# Banks_11_12.net
KiCad netlist of a schematic drawn in Altium Designer
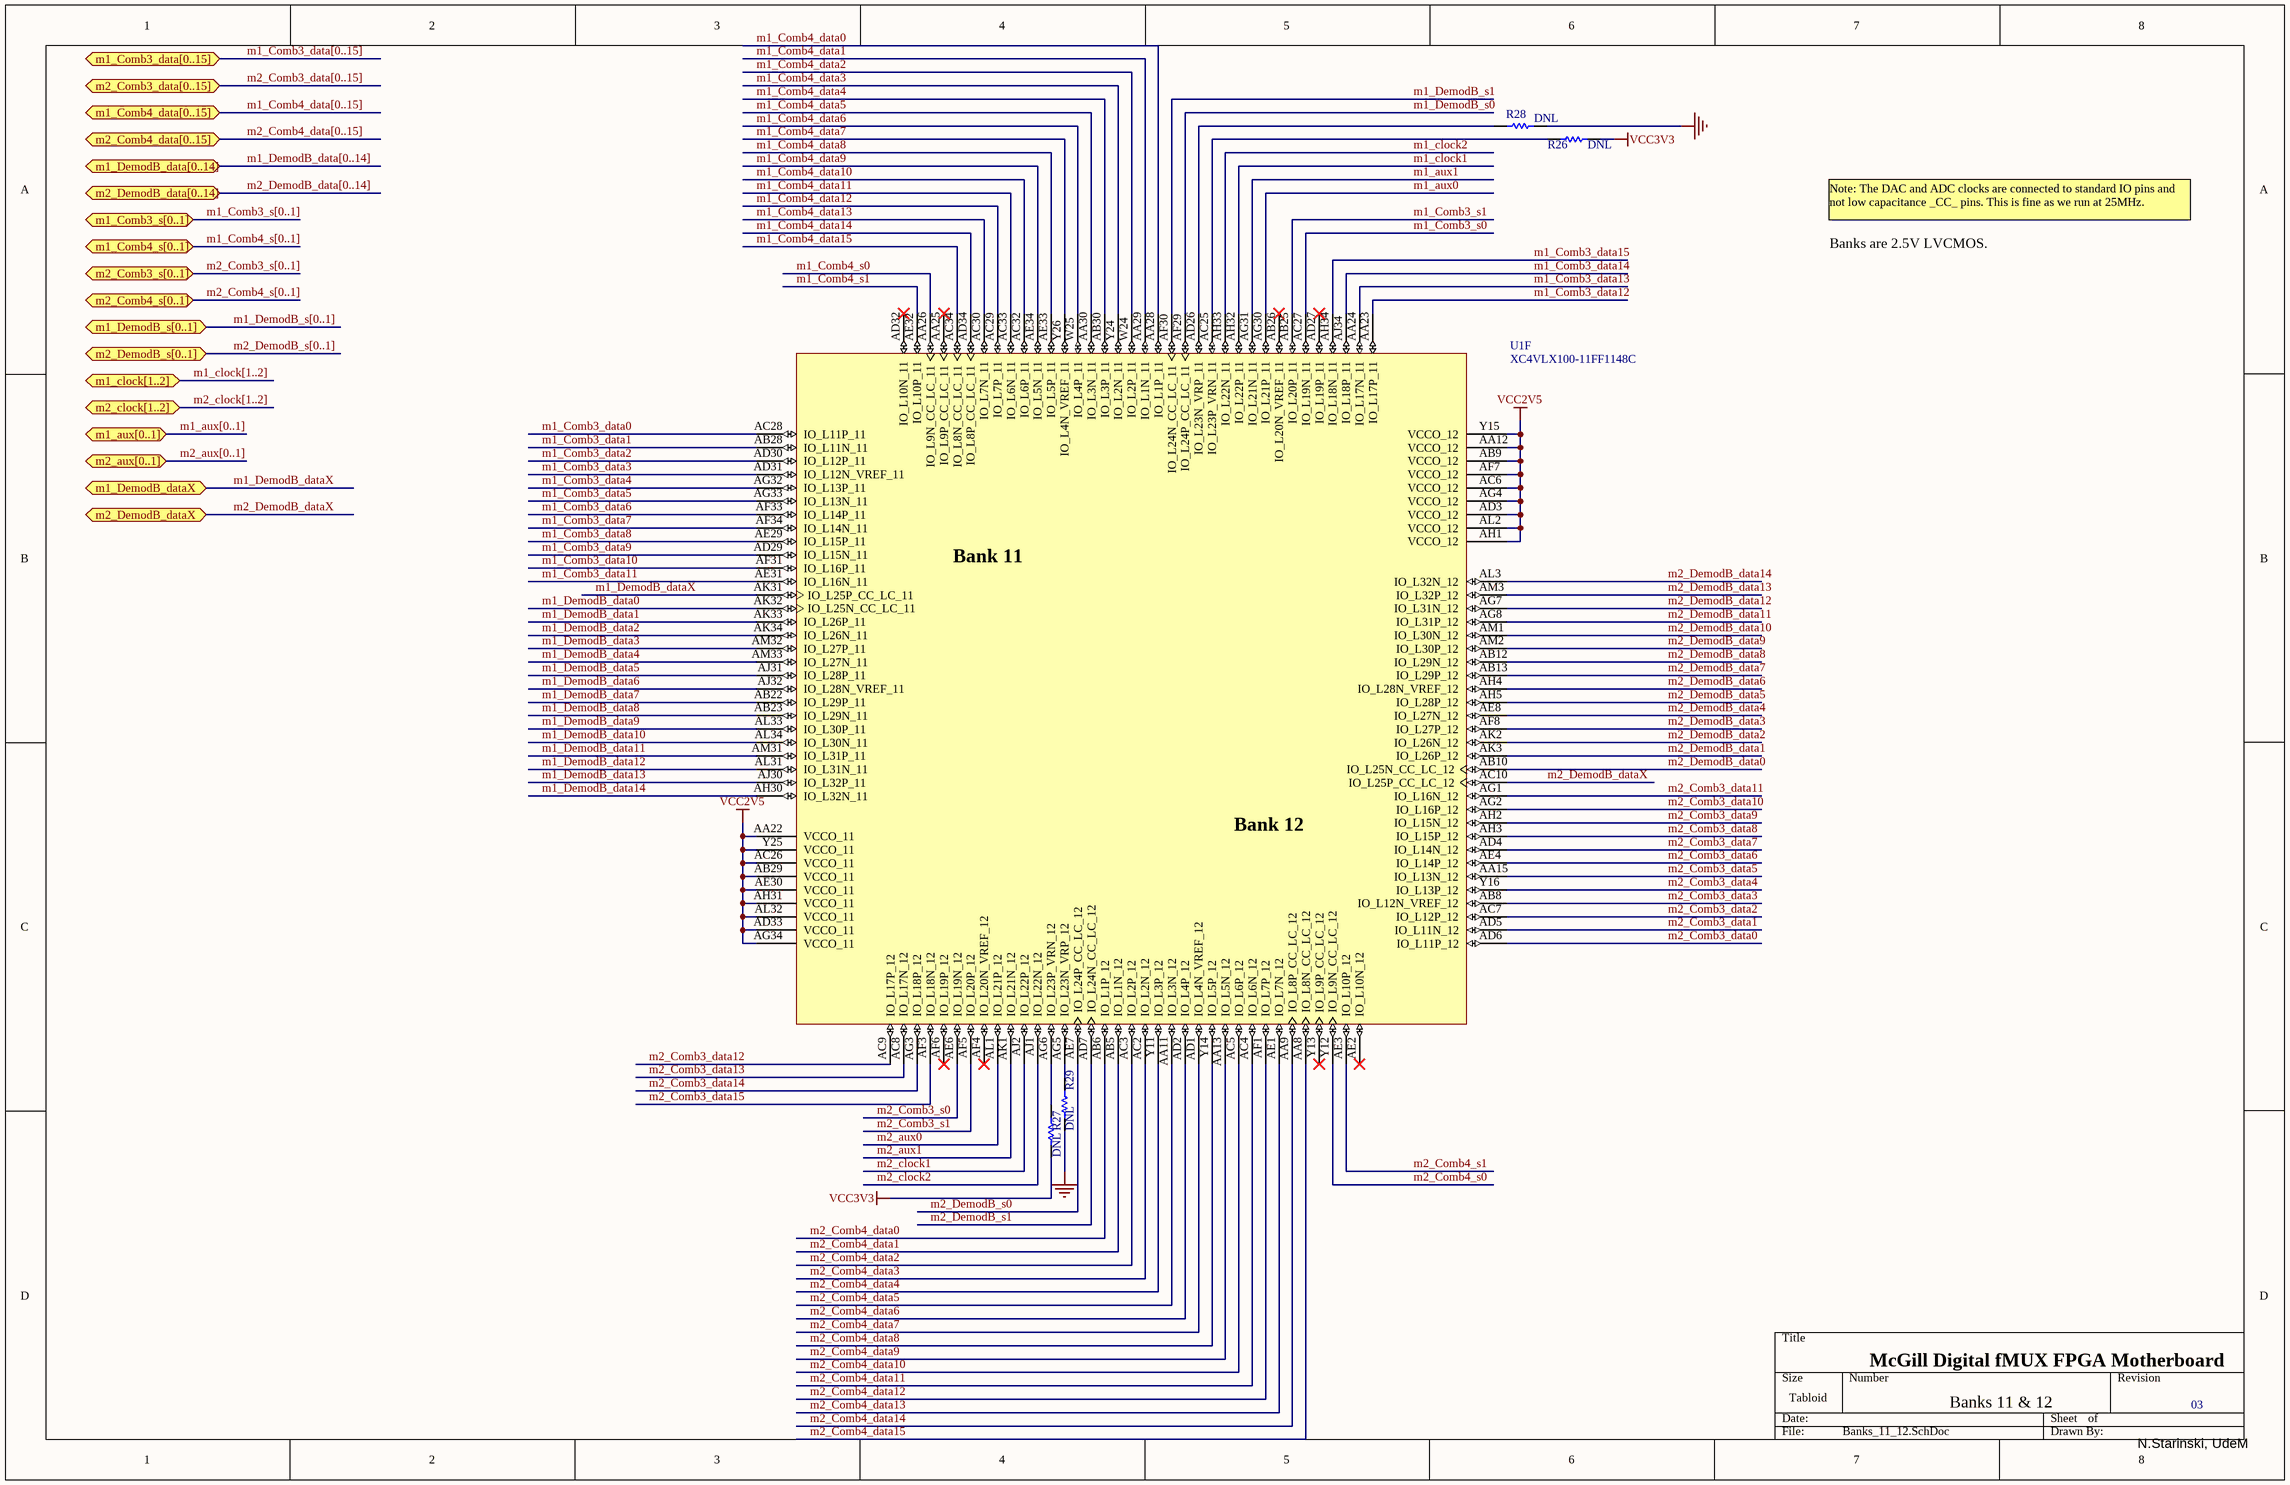
[diagram p0: Banks_11_12.SchDoc]

(export (version "E")
  (design (tool "Eeschema 10.0.6"))
  (components
    (comp (ref "R26")
      (value "DNL")
      (footprint "CR1608-0603")
      (description "Semiconductor Resistor")
      (fields (field (name "PUBLISHER") "Altium Limited"))
      (libsource (lib "Miscellaneous Devices") (part "Res Semi"))
    )
    (comp (ref "R27")
      (value "DNL")
      (footprint "CR1608-0603")
      (description "Semiconductor Resistor")
      (fields (field (name "PUBLISHER") "Altium Limited"))
      (libsource (lib "Miscellaneous Devices") (part "Res Semi"))
    )
    (comp (ref "R28")
      (value "DNL")
      (footprint "CR1608-0603")
      (description "Semiconductor Resistor")
      (fields (field (name "PUBLISHER") "Altium Limited"))
      (libsource (lib "Miscellaneous Devices") (part "Res Semi"))
    )
    (comp (ref "R29")
      (value "DNL")
      (footprint "CR1608-0603")
      (description "Semiconductor Resistor")
      (fields (field (name "PUBLISHER") "Altium Limited"))
      (libsource (lib "Miscellaneous Devices") (part "Res Semi"))
    )
    (comp (ref "U1")
      (value "XC4VLX100-11FF1148C")
      (footprint "FF1148")
      (description "Xilinx Virtex-4 LX Platform FPGA, 1148-Ball FFBGA, Speed Grade 11, 768 User I/Os, Commercial Grade")
      (fields (field (name "PUBLISHER") "Altium Limited"))
      (libsource (lib "Xilinx Virtex-4") (part "XC4VLX100-11FF1148C"))
    )
  )
  (nets
    (net (code "1") (name "/m1_Comb3_data0") (class "Default")
      (node (ref "U1") (pin "AC28") (pinfunction "IO_L11P_11_AC28") (pintype "bidirectional"))
    )
    (net (code "2") (name "/m1_Comb3_data1") (class "Default")
      (node (ref "U1") (pin "AB28") (pinfunction "IO_L11N_11_AB28") (pintype "bidirectional"))
    )
    (net (code "3") (name "/m1_Comb3_data2") (class "Default")
      (node (ref "U1") (pin "AD30") (pinfunction "IO_L12P_11_AD30") (pintype "bidirectional"))
    )
    (net (code "4") (name "/m1_Comb3_data3") (class "Default")
      (node (ref "U1") (pin "AD31") (pinfunction "IO_L12N_VREF_11_AD31") (pintype "bidirectional"))
    )
    (net (code "5") (name "/m1_Comb3_data4") (class "Default")
      (node (ref "U1") (pin "AG32") (pinfunction "IO_L13P_11_AG32") (pintype "bidirectional"))
    )
    (net (code "6") (name "/m1_Comb3_data5") (class "Default")
      (node (ref "U1") (pin "AG33") (pinfunction "IO_L13N_11_AG33") (pintype "bidirectional"))
    )
    (net (code "7") (name "/m1_Comb3_data6") (class "Default")
      (node (ref "U1") (pin "AF33") (pinfunction "IO_L14P_11_AF33") (pintype "bidirectional"))
    )
    (net (code "8") (name "/m1_Comb3_data7") (class "Default")
      (node (ref "U1") (pin "AF34") (pinfunction "IO_L14N_11_AF34") (pintype "bidirectional"))
    )
    (net (code "9") (name "/m1_Comb3_data8") (class "Default")
      (node (ref "U1") (pin "AE29") (pinfunction "IO_L15P_11_AE29") (pintype "bidirectional"))
    )
    (net (code "10") (name "/m1_Comb3_data9") (class "Default")
      (node (ref "U1") (pin "AD29") (pinfunction "IO_L15N_11_AD29") (pintype "bidirectional"))
    )
    (net (code "11") (name "/m1_Comb3_data10") (class "Default")
      (node (ref "U1") (pin "AF31") (pinfunction "IO_L16P_11_AF31") (pintype "bidirectional"))
    )
    (net (code "12") (name "/m1_Comb3_data11") (class "Default")
      (node (ref "U1") (pin "AE31") (pinfunction "IO_L16N_11_AE31") (pintype "bidirectional"))
    )
    (net (code "13") (name "/m1_Comb3_data12") (class "Default")
      (node (ref "U1") (pin "AA23") (pinfunction "IO_L17P_11_AA23") (pintype "bidirectional"))
    )
    (net (code "14") (name "/m1_Comb3_data13") (class "Default")
      (node (ref "U1") (pin "AA24") (pinfunction "IO_L17N_11_AA24") (pintype "bidirectional"))
    )
    (net (code "15") (name "/m1_Comb3_data14") (class "Default")
      (node (ref "U1") (pin "AJ34") (pinfunction "IO_L18P_11_AJ34") (pintype "bidirectional"))
    )
    (net (code "16") (name "/m1_Comb3_data15") (class "Default")
      (node (ref "U1") (pin "AH34") (pinfunction "IO_L18N_11_AH34") (pintype "bidirectional"))
    )
    (net (code "18") (name "/m1_Comb3_s0") (class "Default")
      (node (ref "U1") (pin "AC27") (pinfunction "IO_L19N_11_AC27") (pintype "bidirectional"))
    )
    (net (code "19") (name "/m1_Comb3_s1") (class "Default")
      (node (ref "U1") (pin "AB25") (pinfunction "IO_L20P_11_AB25") (pintype "bidirectional"))
    )
    (net (code "21") (name "/m1_Comb4_data0") (class "Default")
      (node (ref "U1") (pin "AA28") (pinfunction "IO_L1P_11_AA28") (pintype "bidirectional"))
    )
    (net (code "22") (name "/m1_Comb4_data1") (class "Default")
      (node (ref "U1") (pin "AA29") (pinfunction "IO_L1N_11_AA29") (pintype "bidirectional"))
    )
    (net (code "23") (name "/m1_Comb4_data2") (class "Default")
      (node (ref "U1") (pin "W24") (pinfunction "IO_L2P_11_W24") (pintype "bidirectional"))
    )
    (net (code "24") (name "/m1_Comb4_data3") (class "Default")
      (node (ref "U1") (pin "Y24") (pinfunction "IO_L2N_11_Y24") (pintype "bidirectional"))
    )
    (net (code "25") (name "/m1_Comb4_data4") (class "Default")
      (node (ref "U1") (pin "AB30") (pinfunction "IO_L3P_11_AB30") (pintype "bidirectional"))
    )
    (net (code "26") (name "/m1_Comb4_data5") (class "Default")
      (node (ref "U1") (pin "AA30") (pinfunction "IO_L3N_11_AA30") (pintype "bidirectional"))
    )
    (net (code "27") (name "/m1_Comb4_data6") (class "Default")
      (node (ref "U1") (pin "W25") (pinfunction "IO_L4P_11_W25") (pintype "bidirectional"))
    )
    (net (code "28") (name "/m1_Comb4_data7") (class "Default")
      (node (ref "U1") (pin "Y26") (pinfunction "IO_L4N_VREF_11_Y26") (pintype "bidirectional"))
    )
    (net (code "29") (name "/m1_Comb4_data8") (class "Default")
      (node (ref "U1") (pin "AE33") (pinfunction "IO_L5P_11_AE33") (pintype "bidirectional"))
    )
    (net (code "30") (name "/m1_Comb4_data9") (class "Default")
      (node (ref "U1") (pin "AE34") (pinfunction "IO_L5N_11_AE34") (pintype "bidirectional"))
    )
    (net (code "31") (name "/m1_Comb4_data10") (class "Default")
      (node (ref "U1") (pin "AC32") (pinfunction "IO_L6P_11_AC32") (pintype "bidirectional"))
    )
    (net (code "32") (name "/m1_Comb4_data11") (class "Default")
      (node (ref "U1") (pin "AC33") (pinfunction "IO_L6N_11_AC33") (pintype "bidirectional"))
    )
    (net (code "33") (name "/m1_Comb4_data12") (class "Default")
      (node (ref "U1") (pin "AC29") (pinfunction "IO_L7P_11_AC29") (pintype "bidirectional"))
    )
    (net (code "34") (name "/m1_Comb4_data13") (class "Default")
      (node (ref "U1") (pin "AC30") (pinfunction "IO_L7N_11_AC30") (pintype "bidirectional"))
    )
    (net (code "35") (name "/m1_Comb4_data14") (class "Default")
      (node (ref "U1") (pin "AD34") (pinfunction "IO_L8P_CC_LC_11_AD34") (pintype "bidirectional"))
    )
    (net (code "36") (name "/m1_Comb4_data15") (class "Default")
      (node (ref "U1") (pin "AC34") (pinfunction "IO_L8N_CC_LC_11_AC34") (pintype "bidirectional"))
    )
    (net (code "38") (name "/m1_Comb4_s0") (class "Default")
      (node (ref "U1") (pin "AA26") (pinfunction "IO_L9N_CC_LC_11_AA26") (pintype "bidirectional"))
    )
    (net (code "39") (name "/m1_Comb4_s1") (class "Default")
      (node (ref "U1") (pin "AE32") (pinfunction "IO_L10P_11_AE32") (pintype "bidirectional"))
    )
    (net (code "41") (name "/m1_DemodB_data0") (class "Default")
      (node (ref "U1") (pin "AK32") (pinfunction "IO_L25N_CC_LC_11_AK32") (pintype "bidirectional"))
    )
    (net (code "42") (name "/m1_DemodB_data1") (class "Default")
      (node (ref "U1") (pin "AK33") (pinfunction "IO_L26P_11_AK33") (pintype "bidirectional"))
    )
    (net (code "43") (name "/m1_DemodB_data2") (class "Default")
      (node (ref "U1") (pin "AK34") (pinfunction "IO_L26N_11_AK34") (pintype "bidirectional"))
    )
    (net (code "44") (name "/m1_DemodB_data3") (class "Default")
      (node (ref "U1") (pin "AM32") (pinfunction "IO_L27P_11_AM32") (pintype "bidirectional"))
    )
    (net (code "45") (name "/m1_DemodB_data4") (class "Default")
      (node (ref "U1") (pin "AM33") (pinfunction "IO_L27N_11_AM33") (pintype "bidirectional"))
    )
    (net (code "46") (name "/m1_DemodB_data5") (class "Default")
      (node (ref "U1") (pin "AJ31") (pinfunction "IO_L28P_11_AJ31") (pintype "bidirectional"))
    )
    (net (code "47") (name "/m1_DemodB_data6") (class "Default")
      (node (ref "U1") (pin "AJ32") (pinfunction "IO_L28N_VREF_11_AJ32") (pintype "bidirectional"))
    )
    (net (code "48") (name "/m1_DemodB_data7") (class "Default")
      (node (ref "U1") (pin "AB22") (pinfunction "IO_L29P_11_AB22") (pintype "bidirectional"))
    )
    (net (code "49") (name "/m1_DemodB_data8") (class "Default")
      (node (ref "U1") (pin "AB23") (pinfunction "IO_L29N_11_AB23") (pintype "bidirectional"))
    )
    (net (code "50") (name "/m1_DemodB_data9") (class "Default")
      (node (ref "U1") (pin "AL33") (pinfunction "IO_L30P_11_AL33") (pintype "bidirectional"))
    )
    (net (code "51") (name "/m1_DemodB_data10") (class "Default")
      (node (ref "U1") (pin "AL34") (pinfunction "IO_L30N_11_AL34") (pintype "bidirectional"))
    )
    (net (code "52") (name "/m1_DemodB_data11") (class "Default")
      (node (ref "U1") (pin "AM31") (pinfunction "IO_L31P_11_AM31") (pintype "bidirectional"))
    )
    (net (code "53") (name "/m1_DemodB_data12") (class "Default")
      (node (ref "U1") (pin "AL31") (pinfunction "IO_L31N_11_AL31") (pintype "bidirectional"))
    )
    (net (code "54") (name "/m1_DemodB_data13") (class "Default")
      (node (ref "U1") (pin "AJ30") (pinfunction "IO_L32P_11_AJ30") (pintype "bidirectional"))
    )
    (net (code "55") (name "/m1_DemodB_data14") (class "Default")
      (node (ref "U1") (pin "AH30") (pinfunction "IO_L32N_11_AH30") (pintype "bidirectional"))
    )
    (net (code "56") (name "/m1_DemodB_dataX") (class "Default")
      (node (ref "U1") (pin "AK31") (pinfunction "IO_L25P_CC_LC_11_AK31") (pintype "bidirectional"))
    )
    (net (code "58") (name "/m1_DemodB_s0") (class "Default")
      (node (ref "U1") (pin "AF29") (pinfunction "IO_L24P_CC_LC_11_AF29") (pintype "bidirectional"))
    )
    (net (code "59") (name "/m1_DemodB_s1") (class "Default")
      (node (ref "U1") (pin "AF30") (pinfunction "IO_L24N_CC_LC_11_AF30") (pintype "bidirectional"))
    )
    (net (code "61") (name "/m1_aux0") (class "Default")
      (node (ref "U1") (pin "AG30") (pinfunction "IO_L21P_11_AG30") (pintype "bidirectional"))
    )
    (net (code "62") (name "/m1_aux1") (class "Default")
      (node (ref "U1") (pin "AG31") (pinfunction "IO_L21N_11_AG31") (pintype "bidirectional"))
    )
    (net (code "64") (name "/m1_clock1") (class "Default")
      (node (ref "U1") (pin "AH32") (pinfunction "IO_L22P_11_AH32") (pintype "bidirectional"))
    )
    (net (code "65") (name "/m1_clock2") (class "Default")
      (node (ref "U1") (pin "AH33") (pinfunction "IO_L22N_11_AH33") (pintype "bidirectional"))
    )
    (net (code "67") (name "/m2_Comb3_data0") (class "Default")
      (node (ref "U1") (pin "AD6") (pinfunction "IO_L11P_12_AD6") (pintype "bidirectional"))
    )
    (net (code "68") (name "/m2_Comb3_data1") (class "Default")
      (node (ref "U1") (pin "AD5") (pinfunction "IO_L11N_12_AD5") (pintype "bidirectional"))
    )
    (net (code "69") (name "/m2_Comb3_data2") (class "Default")
      (node (ref "U1") (pin "AC7") (pinfunction "IO_L12P_12_AC7") (pintype "bidirectional"))
    )
    (net (code "70") (name "/m2_Comb3_data3") (class "Default")
      (node (ref "U1") (pin "AB8") (pinfunction "IO_L12N_VREF_12_AB8") (pintype "bidirectional"))
    )
    (net (code "71") (name "/m2_Comb3_data4") (class "Default")
      (node (ref "U1") (pin "Y16") (pinfunction "IO_L13P_12_Y16") (pintype "bidirectional"))
    )
    (net (code "72") (name "/m2_Comb3_data5") (class "Default")
      (node (ref "U1") (pin "AA15") (pinfunction "IO_L13N_12_AA15") (pintype "bidirectional"))
    )
    (net (code "73") (name "/m2_Comb3_data6") (class "Default")
      (node (ref "U1") (pin "AE4") (pinfunction "IO_L14P_12_AE4") (pintype "bidirectional"))
    )
    (net (code "74") (name "/m2_Comb3_data7") (class "Default")
      (node (ref "U1") (pin "AD4") (pinfunction "IO_L14N_12_AD4") (pintype "bidirectional"))
    )
    (net (code "75") (name "/m2_Comb3_data8") (class "Default")
      (node (ref "U1") (pin "AH3") (pinfunction "IO_L15P_12_AH3") (pintype "bidirectional"))
    )
    (net (code "76") (name "/m2_Comb3_data9") (class "Default")
      (node (ref "U1") (pin "AH2") (pinfunction "IO_L15N_12_AH2") (pintype "bidirectional"))
    )
    (net (code "77") (name "/m2_Comb3_data10") (class "Default")
      (node (ref "U1") (pin "AG2") (pinfunction "IO_L16P_12_AG2") (pintype "bidirectional"))
    )
    (net (code "78") (name "/m2_Comb3_data11") (class "Default")
      (node (ref "U1") (pin "AG1") (pinfunction "IO_L16N_12_AG1") (pintype "bidirectional"))
    )
    (net (code "79") (name "/m2_Comb3_data12") (class "Default")
      (node (ref "U1") (pin "AC9") (pinfunction "IO_L17P_12_AC9") (pintype "bidirectional"))
    )
    (net (code "80") (name "/m2_Comb3_data13") (class "Default")
      (node (ref "U1") (pin "AC8") (pinfunction "IO_L17N_12_AC8") (pintype "bidirectional"))
    )
    (net (code "81") (name "/m2_Comb3_data14") (class "Default")
      (node (ref "U1") (pin "AG3") (pinfunction "IO_L18P_12_AG3") (pintype "bidirectional"))
    )
    (net (code "82") (name "/m2_Comb3_data15") (class "Default")
      (node (ref "U1") (pin "AF3") (pinfunction "IO_L18N_12_AF3") (pintype "bidirectional"))
    )
    (net (code "84") (name "/m2_Comb3_s0") (class "Default")
      (node (ref "U1") (pin "AE6") (pinfunction "IO_L19N_12_AE6") (pintype "bidirectional"))
    )
    (net (code "85") (name "/m2_Comb3_s1") (class "Default")
      (node (ref "U1") (pin "AF5") (pinfunction "IO_L20P_12_AF5") (pintype "bidirectional"))
    )
    (net (code "87") (name "/m2_Comb4_data0") (class "Default")
      (node (ref "U1") (pin "AB6") (pinfunction "IO_L1P_12_AB6") (pintype "bidirectional"))
    )
    (net (code "88") (name "/m2_Comb4_data1") (class "Default")
      (node (ref "U1") (pin "AB5") (pinfunction "IO_L1N_12_AB5") (pintype "bidirectional"))
    )
    (net (code "89") (name "/m2_Comb4_data2") (class "Default")
      (node (ref "U1") (pin "AC3") (pinfunction "IO_L2P_12_AC3") (pintype "bidirectional"))
    )
    (net (code "90") (name "/m2_Comb4_data3") (class "Default")
      (node (ref "U1") (pin "AC2") (pinfunction "IO_L2N_12_AC2") (pintype "bidirectional"))
    )
    (net (code "91") (name "/m2_Comb4_data4") (class "Default")
      (node (ref "U1") (pin "Y11") (pinfunction "IO_L3P_12_Y11") (pintype "bidirectional"))
    )
    (net (code "92") (name "/m2_Comb4_data5") (class "Default")
      (node (ref "U1") (pin "AA11") (pinfunction "IO_L3N_12_AA11") (pintype "bidirectional"))
    )
    (net (code "93") (name "/m2_Comb4_data6") (class "Default")
      (node (ref "U1") (pin "AD2") (pinfunction "IO_L4P_12_AD2") (pintype "bidirectional"))
    )
    (net (code "94") (name "/m2_Comb4_data7") (class "Default")
      (node (ref "U1") (pin "AD1") (pinfunction "IO_L4N_VREF_12_AD1") (pintype "bidirectional"))
    )
    (net (code "95") (name "/m2_Comb4_data8") (class "Default")
      (node (ref "U1") (pin "Y14") (pinfunction "IO_L5P_12_Y14") (pintype "bidirectional"))
    )
    (net (code "96") (name "/m2_Comb4_data9") (class "Default")
      (node (ref "U1") (pin "AA13") (pinfunction "IO_L5N_12_AA13") (pintype "bidirectional"))
    )
    (net (code "97") (name "/m2_Comb4_data10") (class "Default")
      (node (ref "U1") (pin "AC5") (pinfunction "IO_L6P_12_AC5") (pintype "bidirectional"))
    )
    (net (code "98") (name "/m2_Comb4_data11") (class "Default")
      (node (ref "U1") (pin "AC4") (pinfunction "IO_L6N_12_AC4") (pintype "bidirectional"))
    )
    (net (code "99") (name "/m2_Comb4_data12") (class "Default")
      (node (ref "U1") (pin "AF1") (pinfunction "IO_L7P_12_AF1") (pintype "bidirectional"))
    )
    (net (code "100") (name "/m2_Comb4_data13") (class "Default")
      (node (ref "U1") (pin "AE1") (pinfunction "IO_L7N_12_AE1") (pintype "bidirectional"))
    )
    (net (code "101") (name "/m2_Comb4_data14") (class "Default")
      (node (ref "U1") (pin "AA9") (pinfunction "IO_L8P_CC_LC_12_AA9") (pintype "bidirectional"))
    )
    (net (code "102") (name "/m2_Comb4_data15") (class "Default")
      (node (ref "U1") (pin "AA8") (pinfunction "IO_L8N_CC_LC_12_AA8") (pintype "bidirectional"))
    )
    (net (code "104") (name "/m2_Comb4_s0") (class "Default")
      (node (ref "U1") (pin "Y12") (pinfunction "IO_L9N_CC_LC_12_Y12") (pintype "bidirectional"))
    )
    (net (code "105") (name "/m2_Comb4_s1") (class "Default")
      (node (ref "U1") (pin "AE3") (pinfunction "IO_L10P_12_AE3") (pintype "bidirectional"))
    )
    (net (code "107") (name "/m2_DemodB_data0") (class "Default")
      (node (ref "U1") (pin "AB10") (pinfunction "IO_L25N_CC_LC_12_AB10") (pintype "bidirectional"))
    )
    (net (code "108") (name "/m2_DemodB_data1") (class "Default")
      (node (ref "U1") (pin "AK3") (pinfunction "IO_L26P_12_AK3") (pintype "bidirectional"))
    )
    (net (code "109") (name "/m2_DemodB_data2") (class "Default")
      (node (ref "U1") (pin "AK2") (pinfunction "IO_L26N_12_AK2") (pintype "bidirectional"))
    )
    (net (code "110") (name "/m2_DemodB_data3") (class "Default")
      (node (ref "U1") (pin "AF8") (pinfunction "IO_L27P_12_AF8") (pintype "bidirectional"))
    )
    (net (code "111") (name "/m2_DemodB_data4") (class "Default")
      (node (ref "U1") (pin "AE8") (pinfunction "IO_L27N_12_AE8") (pintype "bidirectional"))
    )
    (net (code "112") (name "/m2_DemodB_data5") (class "Default")
      (node (ref "U1") (pin "AH5") (pinfunction "IO_L28P_12_AH5") (pintype "bidirectional"))
    )
    (net (code "113") (name "/m2_DemodB_data6") (class "Default")
      (node (ref "U1") (pin "AH4") (pinfunction "IO_L28N_VREF_12_AH4") (pintype "bidirectional"))
    )
    (net (code "114") (name "/m2_DemodB_data7") (class "Default")
      (node (ref "U1") (pin "AB13") (pinfunction "IO_L29P_12_AB13") (pintype "bidirectional"))
    )
    (net (code "115") (name "/m2_DemodB_data8") (class "Default")
      (node (ref "U1") (pin "AB12") (pinfunction "IO_L29N_12_AB12") (pintype "bidirectional"))
    )
    (net (code "116") (name "/m2_DemodB_data9") (class "Default")
      (node (ref "U1") (pin "AM2") (pinfunction "IO_L30P_12_AM2") (pintype "bidirectional"))
    )
    (net (code "117") (name "/m2_DemodB_data10") (class "Default")
      (node (ref "U1") (pin "AM1") (pinfunction "IO_L30N_12_AM1") (pintype "bidirectional"))
    )
    (net (code "118") (name "/m2_DemodB_data11") (class "Default")
      (node (ref "U1") (pin "AG8") (pinfunction "IO_L31P_12_AG8") (pintype "bidirectional"))
    )
    (net (code "119") (name "/m2_DemodB_data12") (class "Default")
      (node (ref "U1") (pin "AG7") (pinfunction "IO_L31N_12_AG7") (pintype "bidirectional"))
    )
    (net (code "120") (name "/m2_DemodB_data13") (class "Default")
      (node (ref "U1") (pin "AM3") (pinfunction "IO_L32P_12_AM3") (pintype "bidirectional"))
    )
    (net (code "121") (name "/m2_DemodB_data14") (class "Default")
      (node (ref "U1") (pin "AL3") (pinfunction "IO_L32N_12_AL3") (pintype "bidirectional"))
    )
    (net (code "122") (name "/m2_DemodB_dataX") (class "Default")
      (node (ref "U1") (pin "AC10") (pinfunction "IO_L25P_CC_LC_12_AC10") (pintype "bidirectional"))
    )
    (net (code "124") (name "/m2_DemodB_s0") (class "Default")
      (node (ref "U1") (pin "AE7") (pinfunction "IO_L24P_CC_LC_12_AE7") (pintype "bidirectional"))
    )
    (net (code "125") (name "/m2_DemodB_s1") (class "Default")
      (node (ref "U1") (pin "AD7") (pinfunction "IO_L24N_CC_LC_12_AD7") (pintype "bidirectional"))
    )
    (net (code "127") (name "/m2_aux0") (class "Default")
      (node (ref "U1") (pin "AL1") (pinfunction "IO_L21P_12_AL1") (pintype "bidirectional"))
    )
    (net (code "128") (name "/m2_aux1") (class "Default")
      (node (ref "U1") (pin "AK1") (pinfunction "IO_L21N_12_AK1") (pintype "bidirectional"))
    )
    (net (code "130") (name "/m2_clock1") (class "Default")
      (node (ref "U1") (pin "AJ2") (pinfunction "IO_L22P_12_AJ2") (pintype "bidirectional"))
    )
    (net (code "131") (name "/m2_clock2") (class "Default")
      (node (ref "U1") (pin "AJ1") (pinfunction "IO_L22N_12_AJ1") (pintype "bidirectional"))
    )
    (net (code "133") (name "GND") (class "Default")
      (node (ref "R28") (pin "2") (pinfunction "2_2") (pintype "passive"))
      (node (ref "R29") (pin "1") (pinfunction "1_1") (pintype "passive"))
    )
    (net (code "134") (name "Net-(U1F-IO_L23N_VRP_11)") (class "Default")
      (node (ref "R28") (pin "1") (pinfunction "1_1") (pintype "passive"))
      (node (ref "U1") (pin "AD26") (pinfunction "IO_L23N_VRP_11_AD26") (pintype "bidirectional"))
    )
    (net (code "135") (name "Net-(U1F-IO_L23N_VRP_12)") (class "Default")
      (node (ref "R29") (pin "2") (pinfunction "2_2") (pintype "passive"))
      (node (ref "U1") (pin "AG5") (pinfunction "IO_L23N_VRP_12_AG5") (pintype "bidirectional"))
    )
    (net (code "136") (name "Net-(U1F-IO_L23P_VRN_11)") (class "Default")
      (node (ref "R26") (pin "1") (pinfunction "1_1") (pintype "passive"))
      (node (ref "U1") (pin "AC25") (pinfunction "IO_L23P_VRN_11_AC25") (pintype "bidirectional"))
    )
    (net (code "137") (name "Net-(U1F-IO_L23P_VRN_12)") (class "Default")
      (node (ref "R27") (pin "2") (pinfunction "2_2") (pintype "passive"))
      (node (ref "U1") (pin "AG6") (pinfunction "IO_L23P_VRN_12_AG6") (pintype "bidirectional"))
    )
    (net (code "138") (name "VCC2V5") (class "Default")
      (node (ref "U1") (pin "AA12") (pinfunction "VCCO_12_AA12") (pintype "power_in"))
      (node (ref "U1") (pin "AA22") (pinfunction "VCCO_11_AA22") (pintype "power_in"))
      (node (ref "U1") (pin "AB29") (pinfunction "VCCO_11_AB29") (pintype "power_in"))
      (node (ref "U1") (pin "AB9") (pinfunction "VCCO_12_AB9") (pintype "power_in"))
      (node (ref "U1") (pin "AC26") (pinfunction "VCCO_11_AC26") (pintype "power_in"))
      (node (ref "U1") (pin "AC6") (pinfunction "VCCO_12_AC6") (pintype "power_in"))
      (node (ref "U1") (pin "AD3") (pinfunction "VCCO_12_AD3") (pintype "power_in"))
      (node (ref "U1") (pin "AD33") (pinfunction "VCCO_11_AD33") (pintype "power_in"))
      (node (ref "U1") (pin "AE30") (pinfunction "VCCO_11_AE30") (pintype "power_in"))
      (node (ref "U1") (pin "AF7") (pinfunction "VCCO_12_AF7") (pintype "power_in"))
      (node (ref "U1") (pin "AG34") (pinfunction "VCCO_11_AG34") (pintype "power_in"))
      (node (ref "U1") (pin "AG4") (pinfunction "VCCO_12_AG4") (pintype "power_in"))
      (node (ref "U1") (pin "AH1") (pinfunction "VCCO_12_AH1") (pintype "power_in"))
      (node (ref "U1") (pin "AH31") (pinfunction "VCCO_11_AH31") (pintype "power_in"))
      (node (ref "U1") (pin "AL2") (pinfunction "VCCO_12_AL2") (pintype "power_in"))
      (node (ref "U1") (pin "AL32") (pinfunction "VCCO_11_AL32") (pintype "power_in"))
      (node (ref "U1") (pin "Y15") (pinfunction "VCCO_12_Y15") (pintype "power_in"))
      (node (ref "U1") (pin "Y25") (pinfunction "VCCO_11_Y25") (pintype "power_in"))
    )
    (net (code "139") (name "VCC3V3") (class "Default")
      (node (ref "R26") (pin "2") (pinfunction "2_2") (pintype "passive"))
      (node (ref "R27") (pin "1") (pinfunction "1_1") (pintype "passive"))
    )
    (net (code "140") (name "unconnected-(U1F-IO_L9P_CC_LC_11-PadAA25)") (class "Default")
      (node (ref "U1") (pin "AA25") (pinfunction "IO_L9P_CC_LC_11_AA25") (pintype "bidirectional+no_connect"))
    )
    (net (code "141") (name "unconnected-(U1F-IO_L9P_CC_LC_12-PadY13)") (class "Default")
      (node (ref "U1") (pin "Y13") (pinfunction "IO_L9P_CC_LC_12_Y13") (pintype "bidirectional+no_connect"))
    )
    (net (code "142") (name "unconnected-(U1F-IO_L10N_11-PadAD32)") (class "Default")
      (node (ref "U1") (pin "AD32") (pinfunction "IO_L10N_11_AD32") (pintype "bidirectional+no_connect"))
    )
    (net (code "143") (name "unconnected-(U1F-IO_L10N_12-PadAE2)") (class "Default")
      (node (ref "U1") (pin "AE2") (pinfunction "IO_L10N_12_AE2") (pintype "bidirectional+no_connect"))
    )
    (net (code "144") (name "unconnected-(U1F-IO_L19P_11-PadAD27)") (class "Default")
      (node (ref "U1") (pin "AD27") (pinfunction "IO_L19P_11_AD27") (pintype "bidirectional+no_connect"))
    )
    (net (code "145") (name "unconnected-(U1F-IO_L19P_12-PadAF6)") (class "Default")
      (node (ref "U1") (pin "AF6") (pinfunction "IO_L19P_12_AF6") (pintype "bidirectional+no_connect"))
    )
    (net (code "146") (name "unconnected-(U1F-IO_L20N_VREF_11-PadAB26)") (class "Default")
      (node (ref "U1") (pin "AB26") (pinfunction "IO_L20N_VREF_11_AB26") (pintype "bidirectional+no_connect"))
    )
    (net (code "147") (name "unconnected-(U1F-IO_L20N_VREF_12-PadAF4)") (class "Default")
      (node (ref "U1") (pin "AF4") (pinfunction "IO_L20N_VREF_12_AF4") (pintype "bidirectional+no_connect"))
    )
  )
)
